# v1_1.net
KiCad netlist of a schematic drawn in EAGLE
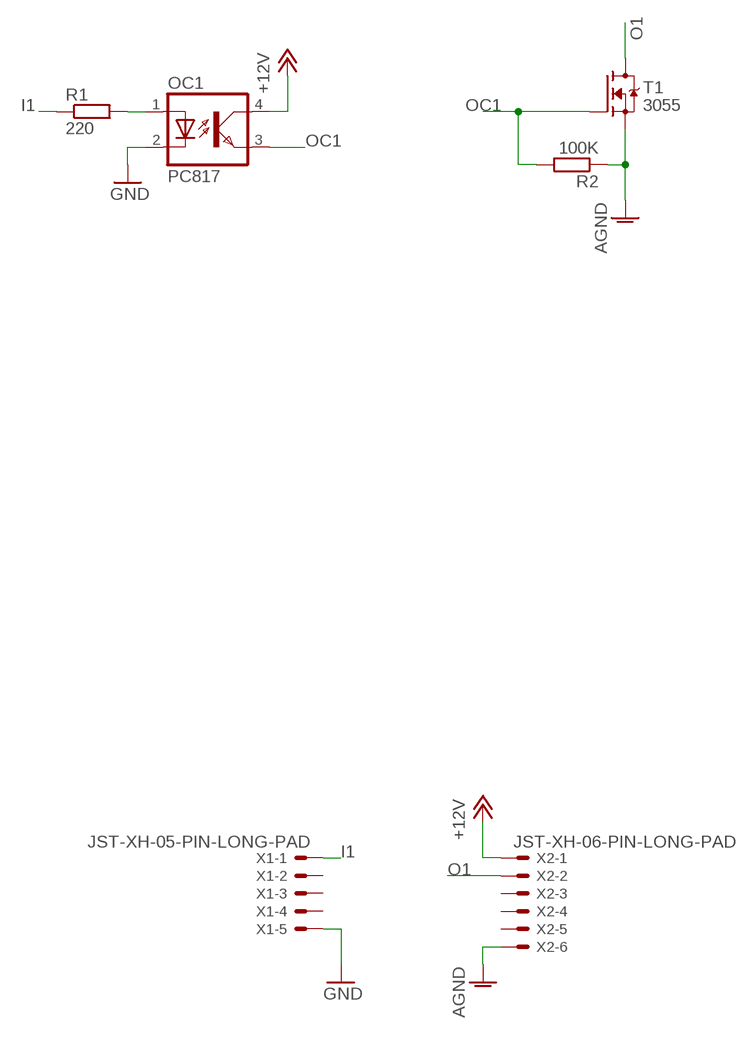
[diagram p0: schematic, sheet 1]

(export (version "E")
  (design (tool "Eeschema 10.0.6"))
  (components
    (comp (ref "OC1")
      (value "PC817")
      (footprint "eagle-import:DIL04")
      (libsource (lib "eagle-import") (part "PC817"))
    )
    (comp (ref "R1")
      (value "220")
      (footprint "eagle-import:R0603")
      (libsource (lib "eagle-import") (part "R-EU_R0603"))
    )
    (comp (ref "R2")
      (value "100K")
      (footprint "eagle-import:R0603")
      (libsource (lib "eagle-import") (part "R-EU_R0603"))
    )
    (comp (ref "T1")
      (value "3055")
      (footprint "eagle-import:SOT223")
      (libsource (lib "eagle-import") (part "MOSFET-N-SOT223"))
    )
    (comp (ref "X1")
      (value "JST-XH-05-PIN-LONG-PAD")
      (footprint "eagle-import:JST-XH-05-PACKAGE-LONG-PAD")
      (libsource (lib "eagle-import") (part "JST-XH-05-PIN-LONG-PAD"))
    )
    (comp (ref "X2")
      (value "JST-XH-06-PIN-LONG-PAD")
      (footprint "eagle-import:JST-XH-06-PACKAGE-LONG-PAD")
      (libsource (lib "eagle-import") (part "JST-XH-06-PIN-LONG-PAD"))
    )
  )
  (nets
    (net (code "1") (name "+12V") (class "Default")
      (node (ref "OC1") (pin "4") (pinfunction "COL_4") (pintype "passive"))
      (node (ref "X2") (pin "1") (pinfunction "S_1") (pintype "passive"))
    )
    (net (code "2") (name "/I1") (class "Default")
      (node (ref "R1") (pin "1") (pinfunction "1_1") (pintype "passive"))
      (node (ref "X1") (pin "1") (pinfunction "S_1") (pintype "passive"))
    )
    (net (code "3") (name "/O1") (class "Default")
      (node (ref "T1") (pin "2") (pinfunction "D_2") (pintype "passive"))
      (node (ref "T1") (pin "4") (pinfunction "D_4") (pintype "passive"))
      (node (ref "X2") (pin "2") (pinfunction "S_2") (pintype "passive"))
    )
    (net (code "4") (name "/OC1") (class "Default")
      (node (ref "OC1") (pin "3") (pinfunction "EMIT_3") (pintype "passive"))
      (node (ref "R2") (pin "2") (pinfunction "2_2") (pintype "passive"))
      (node (ref "T1") (pin "1") (pinfunction "G_1") (pintype "passive"))
    )
    (net (code "5") (name "AGND") (class "Default")
      (node (ref "R2") (pin "1") (pinfunction "1_1") (pintype "passive"))
      (node (ref "T1") (pin "3") (pinfunction "S_3") (pintype "passive"))
      (node (ref "X2") (pin "6") (pinfunction "S_6") (pintype "passive"))
    )
    (net (code "6") (name "GND") (class "Default")
      (node (ref "OC1") (pin "2") (pinfunction "C_2") (pintype "passive"))
      (node (ref "X1") (pin "5") (pinfunction "S_5") (pintype "passive"))
    )
    (net (code "7") (name "Net-(OC1-A)") (class "Default")
      (node (ref "OC1") (pin "1") (pinfunction "A_1") (pintype "passive"))
      (node (ref "R1") (pin "2") (pinfunction "2_2") (pintype "passive"))
    )
    (net (code "8") (name "unconnected-(X1B-S-Pad2)") (class "Default")
      (node (ref "X1") (pin "2") (pinfunction "S_2") (pintype "passive"))
    )
    (net (code "9") (name "unconnected-(X1C-S-Pad3)") (class "Default")
      (node (ref "X1") (pin "3") (pinfunction "S_3") (pintype "passive"))
    )
    (net (code "10") (name "unconnected-(X1D-S-Pad4)") (class "Default")
      (node (ref "X1") (pin "4") (pinfunction "S_4") (pintype "passive"))
    )
    (net (code "11") (name "unconnected-(X2C-S-Pad3)") (class "Default")
      (node (ref "X2") (pin "3") (pinfunction "S_3") (pintype "passive"))
    )
    (net (code "12") (name "unconnected-(X2D-S-Pad4)") (class "Default")
      (node (ref "X2") (pin "4") (pinfunction "S_4") (pintype "passive"))
    )
    (net (code "13") (name "unconnected-(X2E-S-Pad5)") (class "Default")
      (node (ref "X2") (pin "5") (pinfunction "S_5") (pintype "passive"))
    )
  )
)
